# wifi-leds2.net
KiCad netlist of a schematic drawn in EAGLE
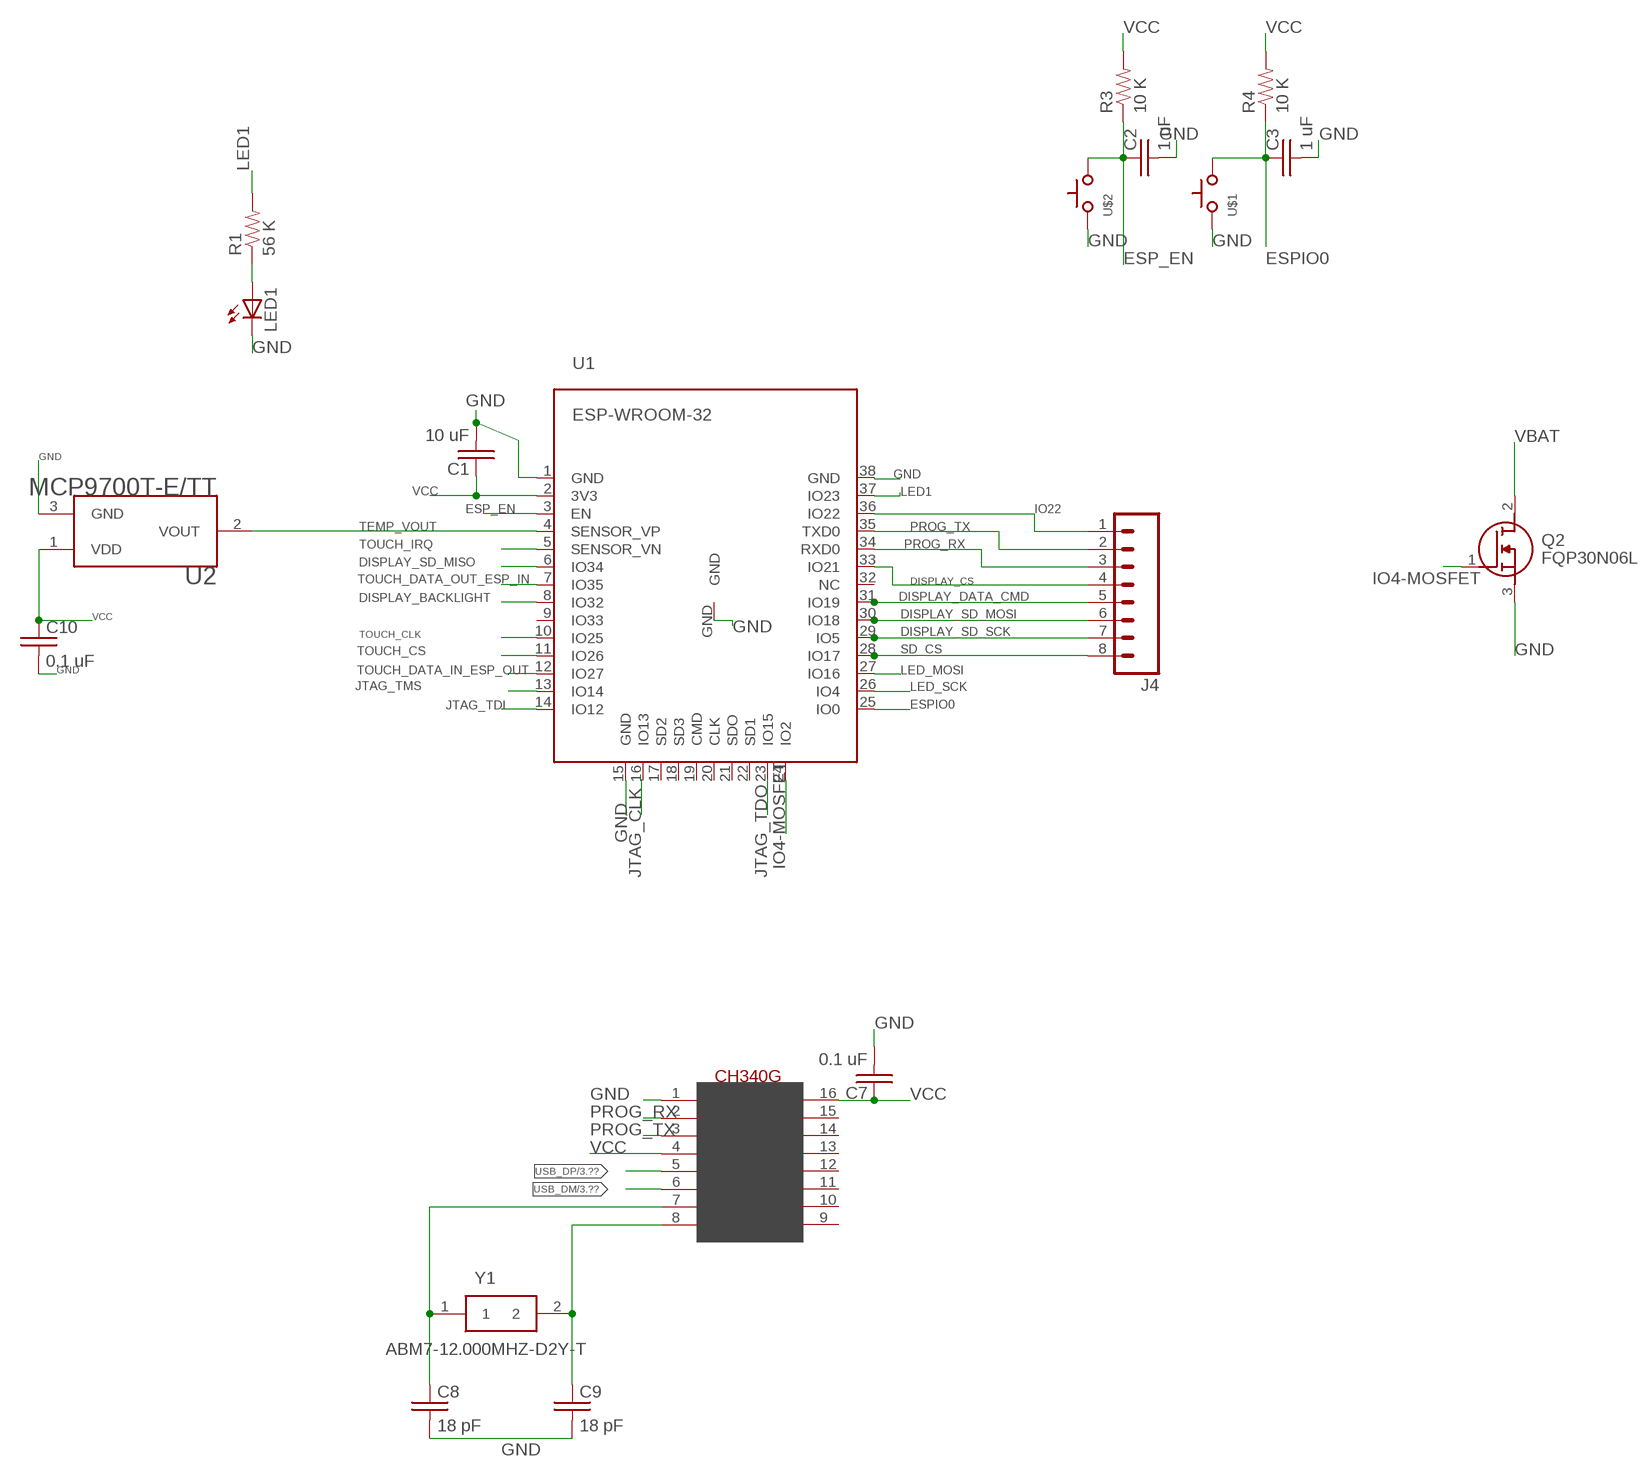
[diagram p0: schematic, sheet 1]
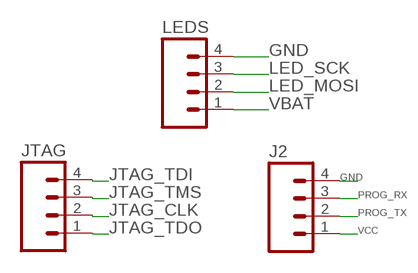
[diagram p1: schematic, sheet 2]
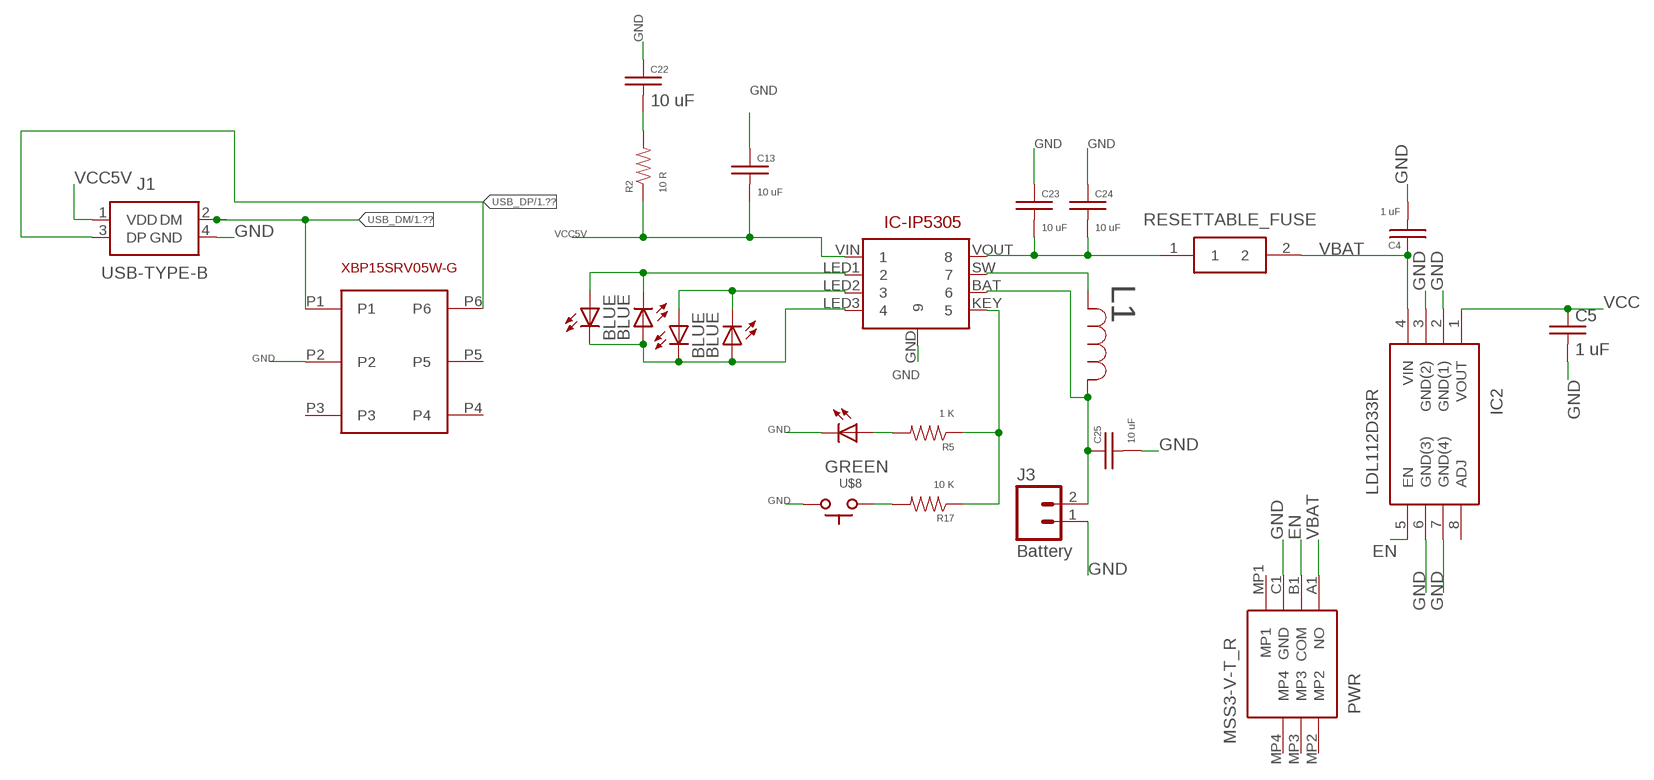
[diagram p2: schematic, sheet 3]
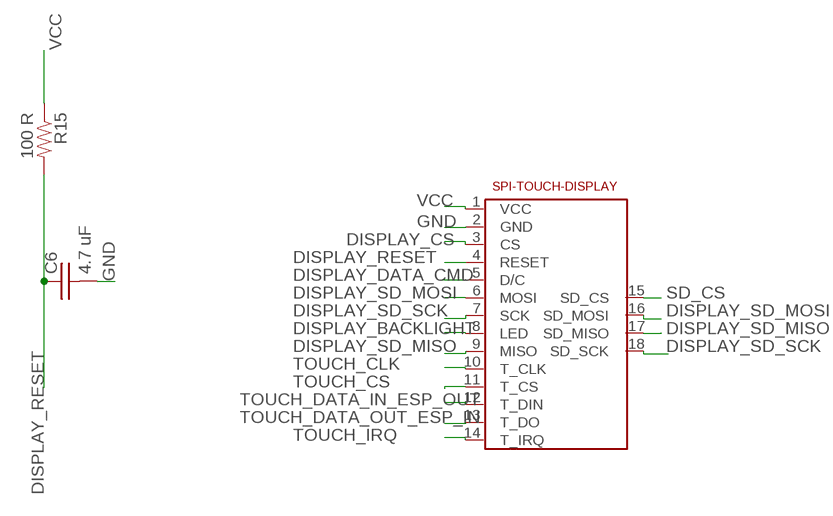
[diagram p3: schematic, sheet 4]
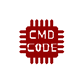
[diagram p4: schematic, sheet 5]

(export (version "E")
  (design (tool "Eeschema 10.0.6"))
  (components
    (comp (ref "U$5")
      (value "CMD_C0DE_LOGOCMD_CODE_LOGO_TOP_COPPER")
      (footprint "eagle-import:CMD_C0DE_LOGO_TOP_COPPER")
      (libsource (lib "eagle-import") (part "CMD_C0DE_LOGOCMD_CODE_LOGO_TOP_COPPER"))
    )
    (comp (ref "C6")
      (value "4.7 uF")
      (footprint "eagle-import:C0805")
      (libsource (lib "eagle-import") (part "C-USC0805"))
    )
    (comp (ref "R15")
      (value "100 R")
      (footprint "eagle-import:0805")
      (libsource (lib "eagle-import") (part "RESISTOR0805-RES"))
    )
    (comp (ref "U$3")
      (value "2.4-SPI-TFT-TOUCH-SSD-MODULE")
      (footprint "eagle-import:2.4-SPI-TFT-TOUCH-SSD-MODULE")
      (libsource (lib "eagle-import") (part "2.4-SPI-TFT-TOUCH-SSD-MODULE"))
    )
    (comp (ref "J2")
      (value "M04PTH")
      (footprint "eagle-import:1X04")
      (libsource (lib "eagle-import") (part "M04PTH"))
    )
    (comp (ref "JTAG")
      (value "M04PTH")
      (footprint "eagle-import:1X04")
      (libsource (lib "eagle-import") (part "M04PTH"))
    )
    (comp (ref "LEDS")
      (value "M04POLAR")
      (footprint "eagle-import:MOLEX-1X4")
      (libsource (lib "eagle-import") (part "M04POLAR"))
    )
    (comp (ref "C1")
      (value "10 uF")
      (footprint "eagle-import:C0805")
      (libsource (lib "eagle-import") (part "C-USC0805"))
    )
    (comp (ref "C2")
      (value "1 uF")
      (footprint "eagle-import:C0805")
      (libsource (lib "eagle-import") (part "C-USC0805"))
    )
    (comp (ref "C3")
      (value "1 uF")
      (footprint "eagle-import:C0805")
      (libsource (lib "eagle-import") (part "C-USC0805"))
    )
    (comp (ref "C7")
      (value "0.1 uF")
      (footprint "eagle-import:C0805")
      (libsource (lib "eagle-import") (part "C-USC0805"))
    )
    (comp (ref "C8")
      (value "18 pF")
      (footprint "eagle-import:C0805")
      (libsource (lib "eagle-import") (part "C-USC0805"))
    )
    (comp (ref "C9")
      (value "18 pF")
      (footprint "eagle-import:C0805")
      (libsource (lib "eagle-import") (part "C-USC0805"))
    )
    (comp (ref "C10")
      (value "0.1 uF")
      (footprint "eagle-import:C0805")
      (libsource (lib "eagle-import") (part "C-USC0805"))
    )
    (comp (ref "J4")
      (value "M08")
      (footprint "eagle-import:1X08_ROUND")
      (libsource (lib "eagle-import") (part "M08"))
    )
    (comp (ref "LED1")
      (value "LED3MM")
      (footprint "eagle-import:LED3MM")
      (libsource (lib "eagle-import") (part "LED3MM"))
    )
    (comp (ref "Q2")
      (value "FQP30N06L")
      (footprint "eagle-import:TO254P470X1016X2019-3P")
      (fields (field (name "MOUSER_PART_NUMBER") "512-FQP30N06L") (field (name "RS_PART_NUMBER") "8075863P"))
      (libsource (lib "eagle-import") (part "FQP30N06L"))
    )
    (comp (ref "R1")
      (value "56 K")
      (footprint "eagle-import:0805")
      (libsource (lib "eagle-import") (part "passives_RESISTOR0805-RES"))
    )
    (comp (ref "R3")
      (value "10 K")
      (footprint "eagle-import:0805")
      (libsource (lib "eagle-import") (part "passives_RESISTOR0805-RES"))
    )
    (comp (ref "R4")
      (value "10 K")
      (footprint "eagle-import:0805")
      (libsource (lib "eagle-import") (part "passives_RESISTOR0805-RES"))
    )
    (comp (ref "U$1")
      (value "SWITCH_TACTILETACTILE-2PIN-NARROW")
      (footprint "eagle-import:TACTILE-2PIN-NARROW")
      (libsource (lib "eagle-import") (part "SWITCH_TACTILETACTILE-2PIN-NARROW"))
    )
    (comp (ref "U$2")
      (value "SWITCH_TACTILETACTILE-2PIN-NARROW")
      (footprint "eagle-import:TACTILE-2PIN-NARROW")
      (libsource (lib "eagle-import") (part "SWITCH_TACTILETACTILE-2PIN-NARROW"))
    )
    (comp (ref "U$6")
      (value "CH340G")
      (footprint "eagle-import:SOIC16")
      (libsource (lib "eagle-import") (part "CH340G"))
    )
    (comp (ref "U1")
      (value "ESP-WROOM-32")
      (footprint "eagle-import:ESP-WROOM-32")
      (libsource (lib "eagle-import") (part "ESP-WROOM-32"))
    )
    (comp (ref "U2")
      (value "MCP9700T-E/TT")
      (footprint "eagle-import:SOT95P237X112-3N")
      (fields (field (name "MF") "Microchip"))
      (libsource (lib "eagle-import") (part "MCP9700T-E/TT"))
    )
    (comp (ref "Y1")
      (value "ABM7-12.000MHZ-D2Y-T")
      (footprint "eagle-import:ABM7")
      (fields
        (field (name "MOUSER_PART_NUMBER") "815-ABM7-12-D2Y-T")
        (field (name "RS_PART_NUMBER") "1710625P")
      )
      (libsource (lib "eagle-import") (part "ABM7-12.000MHZ-D2Y-T"))
    )
    (comp (ref "C4")
      (value "1 uF")
      (footprint "eagle-import:C0805")
      (libsource (lib "eagle-import") (part "C-USC0805"))
    )
    (comp (ref "C5")
      (value "1 uF")
      (footprint "eagle-import:C0805")
      (libsource (lib "eagle-import") (part "C-USC0805"))
    )
    (comp (ref "C13")
      (value "10 uF")
      (footprint "eagle-import:C0805")
      (libsource (lib "eagle-import") (part "C-USC0805"))
    )
    (comp (ref "C22")
      (value "10 uF")
      (footprint "eagle-import:C0805")
      (libsource (lib "eagle-import") (part "C-USC0805"))
    )
    (comp (ref "C23")
      (value "10 uF")
      (footprint "eagle-import:C0805")
      (libsource (lib "eagle-import") (part "C-USC0805"))
    )
    (comp (ref "C24")
      (value "10 uF")
      (footprint "eagle-import:C0805")
      (libsource (lib "eagle-import") (part "C-USC0805"))
    )
    (comp (ref "C25")
      (value "10 uF")
      (footprint "eagle-import:C0805")
      (libsource (lib "eagle-import") (part "C-USC0805"))
    )
    (comp (ref "CL1")
      (value "BLUE")
      (footprint "eagle-import:LED-1206")
      (libsource (lib "eagle-import") (part "LED1206"))
    )
    (comp (ref "CL2")
      (value "BLUE")
      (footprint "eagle-import:LED-1206")
      (libsource (lib "eagle-import") (part "LED1206"))
    )
    (comp (ref "CL3")
      (value "BLUE")
      (footprint "eagle-import:LED-1206")
      (libsource (lib "eagle-import") (part "LED1206"))
    )
    (comp (ref "CL4")
      (value "BLUE")
      (footprint "eagle-import:LED-1206")
      (libsource (lib "eagle-import") (part "LED1206"))
    )
    (comp (ref "IC-IP5305")
      (value "IP5305ESOP8")
      (footprint "eagle-import:SOIC127P600X165-8")
      (libsource (lib "eagle-import") (part "IP5305ESOP8"))
    )
    (comp (ref "IC2")
      (value "LDL112D33R")
      (footprint "eagle-import:SOIC127P600X175-8N")
      (libsource (lib "eagle-import") (part "LDL112D33R"))
    )
    (comp (ref "J1")
      (value "USB-TYPE-B")
      (footprint "eagle-import:61400413321")
      (fields
        (field (name "MANUFACTURER_PART_NUMBER") "61400413321")
        (field (name "MOUSER_PART_NUMBER") "710-61400413321")
      )
      (libsource (lib "eagle-import") (part "USB-TYPE-B"))
    )
    (comp (ref "J3")
      (value "Battery")
      (footprint "eagle-import:JST-2-PTH")
      (libsource (lib "eagle-import") (part "M02JST-PTH-2"))
    )
    (comp (ref "KEYLED")
      (value "GREEN")
      (footprint "eagle-import:LED-1206")
      (libsource (lib "eagle-import") (part "LED1206"))
    )
    (comp (ref "L1")
      (value "2.2uH")
      (footprint "eagle-import:IND_TAIYO_NRS4018")
      (fields (field (name "MANUFACTURER_PART_NUMBER") "NRS4018T2R2MDGJ"))
      (libsource (lib "eagle-import") (part "NRS4018T2R2MDGJ"))
    )
    (comp (ref "PWR")
      (value "MSS3-V-T_R")
      (footprint "eagle-import:MSS3VTR")
      (fields
        (field (name "MANUFACTURER_PART_NUMBER") "MSS3-V-T/R")
        (field (name "MOUSER_PART_NUMBER") "113-MSS3-V-T/R")
      )
      (libsource (lib "eagle-import") (part "MSS3-V-T_R"))
    )
    (comp (ref "R2")
      (value "10 R")
      (footprint "eagle-import:0805")
      (libsource (lib "eagle-import") (part "passives_RESISTOR0805-RES"))
    )
    (comp (ref "R5")
      (value "1 K")
      (footprint "eagle-import:0805")
      (libsource (lib "eagle-import") (part "passives_RESISTOR0805-RES"))
    )
    (comp (ref "R17")
      (value "10 K")
      (footprint "eagle-import:0805")
      (libsource (lib "eagle-import") (part "passives_RESISTOR0805-RES"))
    )
    (comp (ref "RESETTABLE_FUSE")
      (value "0ZCJ0050FF2G")
      (footprint "eagle-import:FUSC3216X55N")
      (libsource (lib "eagle-import") (part "0ZCJ0050FF2G"))
    )
    (comp (ref "U$8")
      (value "SWITCH_TACTILETACTILE-2PIN-NARROW")
      (footprint "eagle-import:TACTILE-2PIN-NARROW")
      (libsource (lib "eagle-import") (part "SWITCH_TACTILETACTILE-2PIN-NARROW"))
    )
    (comp (ref "U$9")
      (value "XBP15SRV05W-G")
      (footprint "eagle-import:SOT-26P-XBP15SRV05W-G")
      (fields (field (name "DIGI_KEY_PART_NUMBER") "893-1422-1-ND"))
      (libsource (lib "eagle-import") (part "XBP15SRV05W-G"))
    )
  )
  (nets
    (net (code "1") (name "DISPLAY_BACKLIGHT") (class "Default")
      (node (ref "U$3") (pin "8") (pinfunction "LED_8") (pintype "bidirectional"))
      (node (ref "U1") (pin "8") (pinfunction "IO32_8") (pintype "bidirectional"))
    )
    (net (code "2") (name "DISPLAY_CS") (class "Default")
      (node (ref "J4") (pin "4") (pinfunction "4_4") (pintype "passive"))
      (node (ref "U$3") (pin "3") (pinfunction "CS_3") (pintype "bidirectional"))
      (node (ref "U1") (pin "33") (pinfunction "IO21_33") (pintype "bidirectional"))
    )
    (net (code "3") (name "DISPLAY_DATA_CMD") (class "Default")
      (node (ref "J4") (pin "5") (pinfunction "5_5") (pintype "passive"))
      (node (ref "U$3") (pin "5") (pinfunction "D/C_5") (pintype "bidirectional"))
      (node (ref "U1") (pin "31") (pinfunction "IO19_31") (pintype "bidirectional"))
    )
    (net (code "4") (name "DISPLAY_RESET") (class "Default")
      (node (ref "C6") (pin "1") (pinfunction "1_1") (pintype "passive"))
      (node (ref "R15") (pin "2") (pinfunction "2_2") (pintype "passive"))
      (node (ref "U$3") (pin "4") (pinfunction "RESET_4") (pintype "bidirectional"))
    )
    (net (code "5") (name "DISPLAY_SD_MISO") (class "Default")
      (node (ref "U$3") (pin "17") (pinfunction "SD_MISO_17") (pintype "bidirectional"))
      (node (ref "U$3") (pin "9") (pinfunction "MISO_9") (pintype "bidirectional"))
      (node (ref "U1") (pin "6") (pinfunction "IO34_6") (pintype "bidirectional"))
    )
    (net (code "6") (name "DISPLAY_SD_MOSI") (class "Default")
      (node (ref "J4") (pin "6") (pinfunction "6_6") (pintype "passive"))
      (node (ref "U$3") (pin "16") (pinfunction "SD_MOSI_16") (pintype "bidirectional"))
      (node (ref "U$3") (pin "6") (pinfunction "MOSI_6") (pintype "bidirectional"))
      (node (ref "U1") (pin "30") (pinfunction "IO18_30") (pintype "bidirectional"))
    )
    (net (code "7") (name "DISPLAY_SD_SCK") (class "Default")
      (node (ref "J4") (pin "7") (pinfunction "7_7") (pintype "passive"))
      (node (ref "U$3") (pin "18") (pinfunction "SD_SCK_18") (pintype "bidirectional"))
      (node (ref "U$3") (pin "7") (pinfunction "SCK_7") (pintype "bidirectional"))
      (node (ref "U1") (pin "29") (pinfunction "IO5_29") (pintype "bidirectional"))
    )
    (net (code "8") (name "EN") (class "Default")
      (node (ref "IC2") (pin "5") (pinfunction "EN_5") (pintype "bidirectional"))
      (node (ref "PWR") (pin "B1") (pinfunction "COM_B1") (pintype "bidirectional"))
    )
    (net (code "9") (name "ESPIO0") (class "Default")
      (node (ref "C3") (pin "1") (pinfunction "1_1") (pintype "passive"))
      (node (ref "R4") (pin "1") (pinfunction "1_1") (pintype "passive"))
      (node (ref "U$1") (pin "P$1") (pinfunction "A_P$1") (pintype "passive"))
      (node (ref "U1") (pin "25") (pinfunction "IO0_25") (pintype "bidirectional"))
    )
    (net (code "10") (name "ESP_EN") (class "Default")
      (node (ref "C2") (pin "1") (pinfunction "1_1") (pintype "passive"))
      (node (ref "R3") (pin "1") (pinfunction "1_1") (pintype "passive"))
      (node (ref "U$2") (pin "P$1") (pinfunction "A_P$1") (pintype "passive"))
      (node (ref "U1") (pin "3") (pinfunction "EN_3") (pintype "bidirectional"))
    )
    (net (code "11") (name "GND") (class "Default")
      (node (ref "C1") (pin "2") (pinfunction "2_2") (pintype "passive"))
      (node (ref "C10") (pin "2") (pinfunction "2_2") (pintype "passive"))
      (node (ref "C13") (pin "1") (pinfunction "1_1") (pintype "passive"))
      (node (ref "C2") (pin "2") (pinfunction "2_2") (pintype "passive"))
      (node (ref "C22") (pin "1") (pinfunction "1_1") (pintype "passive"))
      (node (ref "C23") (pin "1") (pinfunction "1_1") (pintype "passive"))
      (node (ref "C24") (pin "1") (pinfunction "1_1") (pintype "passive"))
      (node (ref "C25") (pin "2") (pinfunction "2_2") (pintype "passive"))
      (node (ref "C3") (pin "2") (pinfunction "2_2") (pintype "passive"))
      (node (ref "C4") (pin "2") (pinfunction "2_2") (pintype "passive"))
      (node (ref "C5") (pin "2") (pinfunction "2_2") (pintype "passive"))
      (node (ref "C6") (pin "2") (pinfunction "2_2") (pintype "passive"))
      (node (ref "C7") (pin "2") (pinfunction "2_2") (pintype "passive"))
      (node (ref "C8") (pin "2") (pinfunction "2_2") (pintype "passive"))
      (node (ref "C9") (pin "2") (pinfunction "2_2") (pintype "passive"))
      (node (ref "IC-IP5305") (pin "GND") (pinfunction "9_GND") (pintype "bidirectional"))
      (node (ref "IC2") (pin "2") (pinfunction "GND(1)_2") (pintype "bidirectional"))
      (node (ref "IC2") (pin "3") (pinfunction "GND(2)_3") (pintype "bidirectional"))
      (node (ref "IC2") (pin "6") (pinfunction "GND(3)_6") (pintype "bidirectional"))
      (node (ref "IC2") (pin "7") (pinfunction "GND(4)_7") (pintype "bidirectional"))
      (node (ref "J1") (pin "4") (pinfunction "GND_4") (pintype "bidirectional"))
      (node (ref "J2") (pin "4") (pinfunction "4_4") (pintype "passive"))
      (node (ref "J3") (pin "1") (pinfunction "1_1") (pintype "passive"))
      (node (ref "KEYLED") (pin "C") (pinfunction "C_C") (pintype "output"))
      (node (ref "LED1") (pin "K") (pinfunction "C_K") (pintype "output"))
      (node (ref "LEDS") (pin "4") (pinfunction "4_4") (pintype "passive"))
      (node (ref "PWR") (pin "C1") (pinfunction "GND_C1") (pintype "bidirectional"))
      (node (ref "Q2") (pin "3") (pinfunction "S_3") (pintype "bidirectional"))
      (node (ref "U$1") (pin "P$2") (pinfunction "C_P$2") (pintype "passive"))
      (node (ref "U$2") (pin "P$2") (pinfunction "C_P$2") (pintype "passive"))
      (node (ref "U$3") (pin "2") (pinfunction "GND_2") (pintype "power_in"))
      (node (ref "U$6") (pin "1") (pinfunction "GND_1") (pintype "bidirectional"))
      (node (ref "U$8") (pin "P$1") (pinfunction "A_P$1") (pintype "passive"))
      (node (ref "U$9") (pin "P2") (pinfunction "P2_P2") (pintype "bidirectional"))
      (node (ref "U1") (pin "1") (pinfunction "GND_1") (pintype "bidirectional"))
      (node (ref "U1") (pin "15") (pinfunction "GND_15") (pintype "bidirectional"))
      (node (ref "U1") (pin "38") (pinfunction "GND_38") (pintype "bidirectional"))
      (node (ref "U1") (pin "GND") (pinfunction "GND_GND") (pintype "bidirectional"))
      (node (ref "U2") (pin "3") (pinfunction "GND_3") (pintype "power_in"))
    )
    (net (code "12") (name "IO4-MOSFET") (class "Default")
      (node (ref "Q2") (pin "1") (pinfunction "G_1") (pintype "bidirectional"))
      (node (ref "U1") (pin "24") (pinfunction "IO2_24") (pintype "bidirectional"))
    )
    (net (code "13") (name "IO22") (class "Default")
      (node (ref "J4") (pin "1") (pinfunction "1_1") (pintype "passive"))
      (node (ref "U1") (pin "36") (pinfunction "IO22_36") (pintype "bidirectional"))
    )
    (net (code "14") (name "JTAG_CLK") (class "Default")
      (node (ref "JTAG") (pin "2") (pinfunction "2_2") (pintype "passive"))
      (node (ref "U1") (pin "16") (pinfunction "IO13_16") (pintype "bidirectional"))
    )
    (net (code "15") (name "JTAG_TDI") (class "Default")
      (node (ref "JTAG") (pin "4") (pinfunction "4_4") (pintype "passive"))
      (node (ref "U1") (pin "14") (pinfunction "IO12_14") (pintype "bidirectional"))
    )
    (net (code "16") (name "JTAG_TDO") (class "Default")
      (node (ref "JTAG") (pin "1") (pinfunction "1_1") (pintype "passive"))
      (node (ref "U1") (pin "23") (pinfunction "IO15_23") (pintype "bidirectional"))
    )
    (net (code "17") (name "JTAG_TMS") (class "Default")
      (node (ref "JTAG") (pin "3") (pinfunction "3_3") (pintype "passive"))
      (node (ref "U1") (pin "13") (pinfunction "IO14_13") (pintype "bidirectional"))
    )
    (net (code "18") (name "LED1") (class "Default")
      (node (ref "R1") (pin "2") (pinfunction "2_2") (pintype "passive"))
      (node (ref "U1") (pin "37") (pinfunction "IO23_37") (pintype "bidirectional"))
    )
    (net (code "19") (name "LED_MOSI") (class "Default")
      (node (ref "LEDS") (pin "2") (pinfunction "2_2") (pintype "passive"))
      (node (ref "U1") (pin "27") (pinfunction "IO16_27") (pintype "bidirectional"))
    )
    (net (code "20") (name "LED_SCK") (class "Default")
      (node (ref "LEDS") (pin "3") (pinfunction "3_3") (pintype "passive"))
      (node (ref "U1") (pin "26") (pinfunction "IO4_26") (pintype "bidirectional"))
    )
    (net (code "21") (name "Net-(C22-Pad2)") (class "Default")
      (node (ref "C22") (pin "2") (pinfunction "2_2") (pintype "passive"))
      (node (ref "R2") (pin "2") (pinfunction "2_2") (pintype "passive"))
    )
    (net (code "22") (name "Net-(IC-IP5305-2)") (class "Default")
      (node (ref "CL1") (pin "A") (pinfunction "A_A") (pintype "input"))
      (node (ref "CL2") (pin "C") (pinfunction "C_C") (pintype "output"))
      (node (ref "IC-IP5305") (pin "LED1") (pinfunction "2_LED1") (pintype "output"))
    )
    (net (code "23") (name "Net-(IC-IP5305-3)") (class "Default")
      (node (ref "CL3") (pin "A") (pinfunction "A_A") (pintype "input"))
      (node (ref "CL4") (pin "C") (pinfunction "C_C") (pintype "output"))
      (node (ref "IC-IP5305") (pin "LED2") (pinfunction "3_LED2") (pintype "output"))
    )
    (net (code "24") (name "Net-(IC-IP5305-4)") (class "Default")
      (node (ref "CL1") (pin "C") (pinfunction "C_C") (pintype "output"))
      (node (ref "CL2") (pin "A") (pinfunction "A_A") (pintype "input"))
      (node (ref "CL3") (pin "C") (pinfunction "C_C") (pintype "output"))
      (node (ref "CL4") (pin "A") (pinfunction "A_A") (pintype "input"))
      (node (ref "IC-IP5305") (pin "LED3") (pinfunction "4_LED3") (pintype "output"))
    )
    (net (code "25") (name "Net-(IC-IP5305-5)") (class "Default")
      (node (ref "IC-IP5305") (pin "KEY") (pinfunction "5_KEY") (pintype "bidirectional"))
      (node (ref "R17") (pin "1") (pinfunction "1_1") (pintype "passive"))
      (node (ref "R5") (pin "1") (pinfunction "1_1") (pintype "passive"))
    )
    (net (code "26") (name "Net-(IC-IP5305-6)") (class "Default")
      (node (ref "C25") (pin "1") (pinfunction "1_1") (pintype "passive"))
      (node (ref "IC-IP5305") (pin "BAT") (pinfunction "6_BAT") (pintype "bidirectional"))
      (node (ref "J3") (pin "2") (pinfunction "2_2") (pintype "passive"))
      (node (ref "L1") (pin "1") (pinfunction "1_1") (pintype "passive"))
    )
    (net (code "27") (name "Net-(IC-IP5305-7)") (class "Default")
      (node (ref "IC-IP5305") (pin "SW") (pinfunction "7_SW") (pintype "bidirectional"))
      (node (ref "L1") (pin "2") (pinfunction "2_2") (pintype "passive"))
    )
    (net (code "28") (name "Net-(IC-IP5305-8)") (class "Default")
      (node (ref "C23") (pin "2") (pinfunction "2_2") (pintype "passive"))
      (node (ref "C24") (pin "2") (pinfunction "2_2") (pintype "passive"))
      (node (ref "IC-IP5305") (pin "VOUT") (pinfunction "8_VOUT") (pintype "bidirectional"))
      (node (ref "RESETTABLE_FUSE") (pin "1") (pinfunction "1_1") (pintype "passive"))
    )
    (net (code "29") (name "Net-(KEYLED-PadA)") (class "Default")
      (node (ref "KEYLED") (pin "A") (pinfunction "A_A") (pintype "input"))
      (node (ref "R5") (pin "2") (pinfunction "2_2") (pintype "passive"))
    )
    (net (code "30") (name "Net-(LED1-PadA)") (class "Default")
      (node (ref "LED1") (pin "A") (pinfunction "A_A") (pintype "input"))
      (node (ref "R1") (pin "1") (pinfunction "1_1") (pintype "passive"))
    )
    (net (code "31") (name "Net-(U$6-XI)") (class "Default")
      (node (ref "C8") (pin "1") (pinfunction "1_1") (pintype "passive"))
      (node (ref "U$6") (pin "7") (pinfunction "XI_7") (pintype "bidirectional"))
      (node (ref "Y1") (pin "1") (pinfunction "1_1") (pintype "bidirectional"))
    )
    (net (code "32") (name "Net-(U$6-XO)") (class "Default")
      (node (ref "C9") (pin "1") (pinfunction "1_1") (pintype "passive"))
      (node (ref "U$6") (pin "8") (pinfunction "XO_8") (pintype "bidirectional"))
      (node (ref "Y1") (pin "2") (pinfunction "2_2") (pintype "bidirectional"))
    )
    (net (code "33") (name "Net-(U$8-C)") (class "Default")
      (node (ref "R17") (pin "2") (pinfunction "2_2") (pintype "passive"))
      (node (ref "U$8") (pin "P$2") (pinfunction "C_P$2") (pintype "passive"))
    )
    (net (code "34") (name "PROG_RX") (class "Default")
      (node (ref "J2") (pin "3") (pinfunction "3_3") (pintype "passive"))
      (node (ref "J4") (pin "3") (pinfunction "3_3") (pintype "passive"))
      (node (ref "U$6") (pin "2") (pinfunction "TX_2") (pintype "bidirectional"))
      (node (ref "U1") (pin "34") (pinfunction "RXD0_34") (pintype "bidirectional"))
    )
    (net (code "35") (name "PROG_TX") (class "Default")
      (node (ref "J2") (pin "2") (pinfunction "2_2") (pintype "passive"))
      (node (ref "J4") (pin "2") (pinfunction "2_2") (pintype "passive"))
      (node (ref "U$6") (pin "3") (pinfunction "RX_3") (pintype "bidirectional"))
      (node (ref "U1") (pin "35") (pinfunction "TXD0_35") (pintype "bidirectional"))
    )
    (net (code "36") (name "SD_CS") (class "Default")
      (node (ref "J4") (pin "8") (pinfunction "8_8") (pintype "passive"))
      (node (ref "U$3") (pin "15") (pinfunction "SD_CS_15") (pintype "bidirectional"))
      (node (ref "U1") (pin "28") (pinfunction "IO17_28") (pintype "bidirectional"))
    )
    (net (code "37") (name "TEMP_VOUT") (class "Default")
      (node (ref "U1") (pin "4") (pinfunction "SENSOR_VP_4") (pintype "bidirectional"))
      (node (ref "U2") (pin "2") (pinfunction "VOUT_2") (pintype "output"))
    )
    (net (code "38") (name "TOUCH_CLK") (class "Default")
      (node (ref "U$3") (pin "10") (pinfunction "T_CLK_10") (pintype "bidirectional"))
      (node (ref "U1") (pin "10") (pinfunction "IO25_10") (pintype "bidirectional"))
    )
    (net (code "39") (name "TOUCH_CS") (class "Default")
      (node (ref "U$3") (pin "11") (pinfunction "T_CS_11") (pintype "bidirectional"))
      (node (ref "U1") (pin "11") (pinfunction "IO26_11") (pintype "bidirectional"))
    )
    (net (code "40") (name "TOUCH_DATA_IN_ESP_OUT") (class "Default")
      (node (ref "U$3") (pin "12") (pinfunction "T_DIN_12") (pintype "bidirectional"))
      (node (ref "U1") (pin "12") (pinfunction "IO27_12") (pintype "bidirectional"))
    )
    (net (code "41") (name "TOUCH_DATA_OUT_ESP_IN") (class "Default")
      (node (ref "U$3") (pin "13") (pinfunction "T_DO_13") (pintype "bidirectional"))
      (node (ref "U1") (pin "7") (pinfunction "IO35_7") (pintype "bidirectional"))
    )
    (net (code "42") (name "TOUCH_IRQ") (class "Default")
      (node (ref "U$3") (pin "14") (pinfunction "T_IRQ_14") (pintype "bidirectional"))
      (node (ref "U1") (pin "5") (pinfunction "SENSOR_VN_5") (pintype "bidirectional"))
    )
    (net (code "43") (name "USB_DM") (class "Default")
      (node (ref "J1") (pin "2") (pinfunction "DM_2") (pintype "bidirectional"))
      (node (ref "U$6") (pin "6") (pinfunction "D-_6") (pintype "bidirectional"))
      (node (ref "U$9") (pin "P1") (pinfunction "P1_P1") (pintype "bidirectional"))
    )
    (net (code "44") (name "USB_DP") (class "Default")
      (node (ref "J1") (pin "3") (pinfunction "DP_3") (pintype "bidirectional"))
      (node (ref "U$6") (pin "5") (pinfunction "D+_5") (pintype "bidirectional"))
      (node (ref "U$9") (pin "P6") (pinfunction "P6_P6") (pintype "bidirectional"))
    )
    (net (code "45") (name "VBAT") (class "Default")
      (node (ref "C4") (pin "1") (pinfunction "1_1") (pintype "passive"))
      (node (ref "IC2") (pin "4") (pinfunction "VIN_4") (pintype "bidirectional"))
      (node (ref "LEDS") (pin "1") (pinfunction "1_1") (pintype "passive"))
      (node (ref "PWR") (pin "A1") (pinfunction "NO_A1") (pintype "bidirectional"))
      (node (ref "Q2") (pin "2") (pinfunction "D_2") (pintype "bidirectional"))
      (node (ref "RESETTABLE_FUSE") (pin "2") (pinfunction "2_2") (pintype "passive"))
    )
    (net (code "46") (name "VCC") (class "Default")
      (node (ref "C1") (pin "1") (pinfunction "1_1") (pintype "passive"))
      (node (ref "C10") (pin "1") (pinfunction "1_1") (pintype "passive"))
      (node (ref "C5") (pin "1") (pinfunction "1_1") (pintype "passive"))
      (node (ref "C7") (pin "1") (pinfunction "1_1") (pintype "passive"))
      (node (ref "IC2") (pin "1") (pinfunction "VOUT_1") (pintype "bidirectional"))
      (node (ref "J2") (pin "1") (pinfunction "1_1") (pintype "passive"))
      (node (ref "R15") (pin "1") (pinfunction "1_1") (pintype "passive"))
      (node (ref "R3") (pin "2") (pinfunction "2_2") (pintype "passive"))
      (node (ref "R4") (pin "2") (pinfunction "2_2") (pintype "passive"))
      (node (ref "U$3") (pin "1") (pinfunction "VCC_1") (pintype "power_in"))
      (node (ref "U$6") (pin "16") (pinfunction "VCC_16") (pintype "bidirectional"))
      (node (ref "U$6") (pin "4") (pinfunction "V3_4") (pintype "bidirectional"))
      (node (ref "U1") (pin "2") (pinfunction "3V3_2") (pintype "bidirectional"))
      (node (ref "U2") (pin "1") (pinfunction "VDD_1") (pintype "power_in"))
    )
    (net (code "47") (name "VCC5V") (class "Default")
      (node (ref "C13") (pin "2") (pinfunction "2_2") (pintype "passive"))
      (node (ref "IC-IP5305") (pin "VIN") (pinfunction "1_VIN") (pintype "power_in"))
      (node (ref "J1") (pin "1") (pinfunction "VDD_1") (pintype "bidirectional"))
      (node (ref "R2") (pin "1") (pinfunction "1_1") (pintype "passive"))
    )
    (net (code "48") (name "unconnected-(IC2-ADJ-Pad8)") (class "Default")
      (node (ref "IC2") (pin "8") (pinfunction "ADJ_8") (pintype "bidirectional"))
    )
    (net (code "49") (name "unconnected-(PWR-PadMP1)") (class "Default")
      (node (ref "PWR") (pin "MP1") (pinfunction "MP1_MP1") (pintype "bidirectional"))
    )
    (net (code "50") (name "unconnected-(PWR-PadMP2)") (class "Default")
      (node (ref "PWR") (pin "MP2") (pinfunction "MP2_MP2") (pintype "bidirectional"))
    )
    (net (code "51") (name "unconnected-(PWR-PadMP3)") (class "Default")
      (node (ref "PWR") (pin "MP3") (pinfunction "MP3_MP3") (pintype "bidirectional"))
    )
    (net (code "52") (name "unconnected-(PWR-PadMP4)") (class "Default")
      (node (ref "PWR") (pin "MP4") (pinfunction "MP4_MP4") (pintype "bidirectional"))
    )
    (net (code "53") (name "unconnected-(U$6-CTS-Pad9)") (class "Default")
      (node (ref "U$6") (pin "9") (pinfunction "CTS_9") (pintype "bidirectional"))
    )
    (net (code "54") (name "unconnected-(U$6-DCD-Pad12)") (class "Default")
      (node (ref "U$6") (pin "12") (pinfunction "DCD_12") (pintype "bidirectional"))
    )
    (net (code "55") (name "unconnected-(U$6-DSR-Pad10)") (class "Default")
      (node (ref "U$6") (pin "10") (pinfunction "DSR_10") (pintype "bidirectional"))
    )
    (net (code "56") (name "unconnected-(U$6-DTR-Pad13)") (class "Default")
      (node (ref "U$6") (pin "13") (pinfunction "DTR_13") (pintype "bidirectional"))
    )
    (net (code "57") (name "unconnected-(U$6-RI-Pad11)") (class "Default")
      (node (ref "U$6") (pin "11") (pinfunction "RI_11") (pintype "bidirectional"))
    )
    (net (code "58") (name "unconnected-(U$6-RS232-Pad15)") (class "Default")
      (node (ref "U$6") (pin "15") (pinfunction "RS232_15") (pintype "bidirectional"))
    )
    (net (code "59") (name "unconnected-(U$6-RTS-Pad14)") (class "Default")
      (node (ref "U$6") (pin "14") (pinfunction "RTS_14") (pintype "bidirectional"))
    )
    (net (code "60") (name "unconnected-(U$9-PadP3)") (class "Default")
      (node (ref "U$9") (pin "P3") (pinfunction "P3_P3") (pintype "bidirectional"))
    )
    (net (code "61") (name "unconnected-(U$9-PadP4)") (class "Default")
      (node (ref "U$9") (pin "P4") (pinfunction "P4_P4") (pintype "bidirectional"))
    )
    (net (code "62") (name "unconnected-(U$9-PadP5)") (class "Default")
      (node (ref "U$9") (pin "P5") (pinfunction "P5_P5") (pintype "bidirectional"))
    )
    (net (code "63") (name "unconnected-(U1-CLK-Pad20)") (class "Default")
      (node (ref "U1") (pin "20") (pinfunction "CLK_20") (pintype "bidirectional"))
    )
    (net (code "64") (name "unconnected-(U1-CMD-Pad19)") (class "Default")
      (node (ref "U1") (pin "19") (pinfunction "CMD_19") (pintype "bidirectional"))
    )
    (net (code "65") (name "unconnected-(U1-IO33-Pad9)") (class "Default")
      (node (ref "U1") (pin "9") (pinfunction "IO33_9") (pintype "bidirectional"))
    )
    (net (code "66") (name "unconnected-(U1-NC-Pad32)") (class "Default")
      (node (ref "U1") (pin "32") (pinfunction "NC_32") (pintype "bidirectional"))
    )
    (net (code "67") (name "unconnected-(U1-SD1-Pad22)") (class "Default")
      (node (ref "U1") (pin "22") (pinfunction "SD1_22") (pintype "bidirectional"))
    )
    (net (code "68") (name "unconnected-(U1-SD2-Pad17)") (class "Default")
      (node (ref "U1") (pin "17") (pinfunction "SD2_17") (pintype "bidirectional"))
    )
    (net (code "69") (name "unconnected-(U1-SD3-Pad18)") (class "Default")
      (node (ref "U1") (pin "18") (pinfunction "SD3_18") (pintype "bidirectional"))
    )
    (net (code "70") (name "unconnected-(U1-SDO-Pad21)") (class "Default")
      (node (ref "U1") (pin "21") (pinfunction "SDO_21") (pintype "bidirectional"))
    )
  )
)
